# newwind.net
KiCad netlist of a schematic drawn in Altium Designer
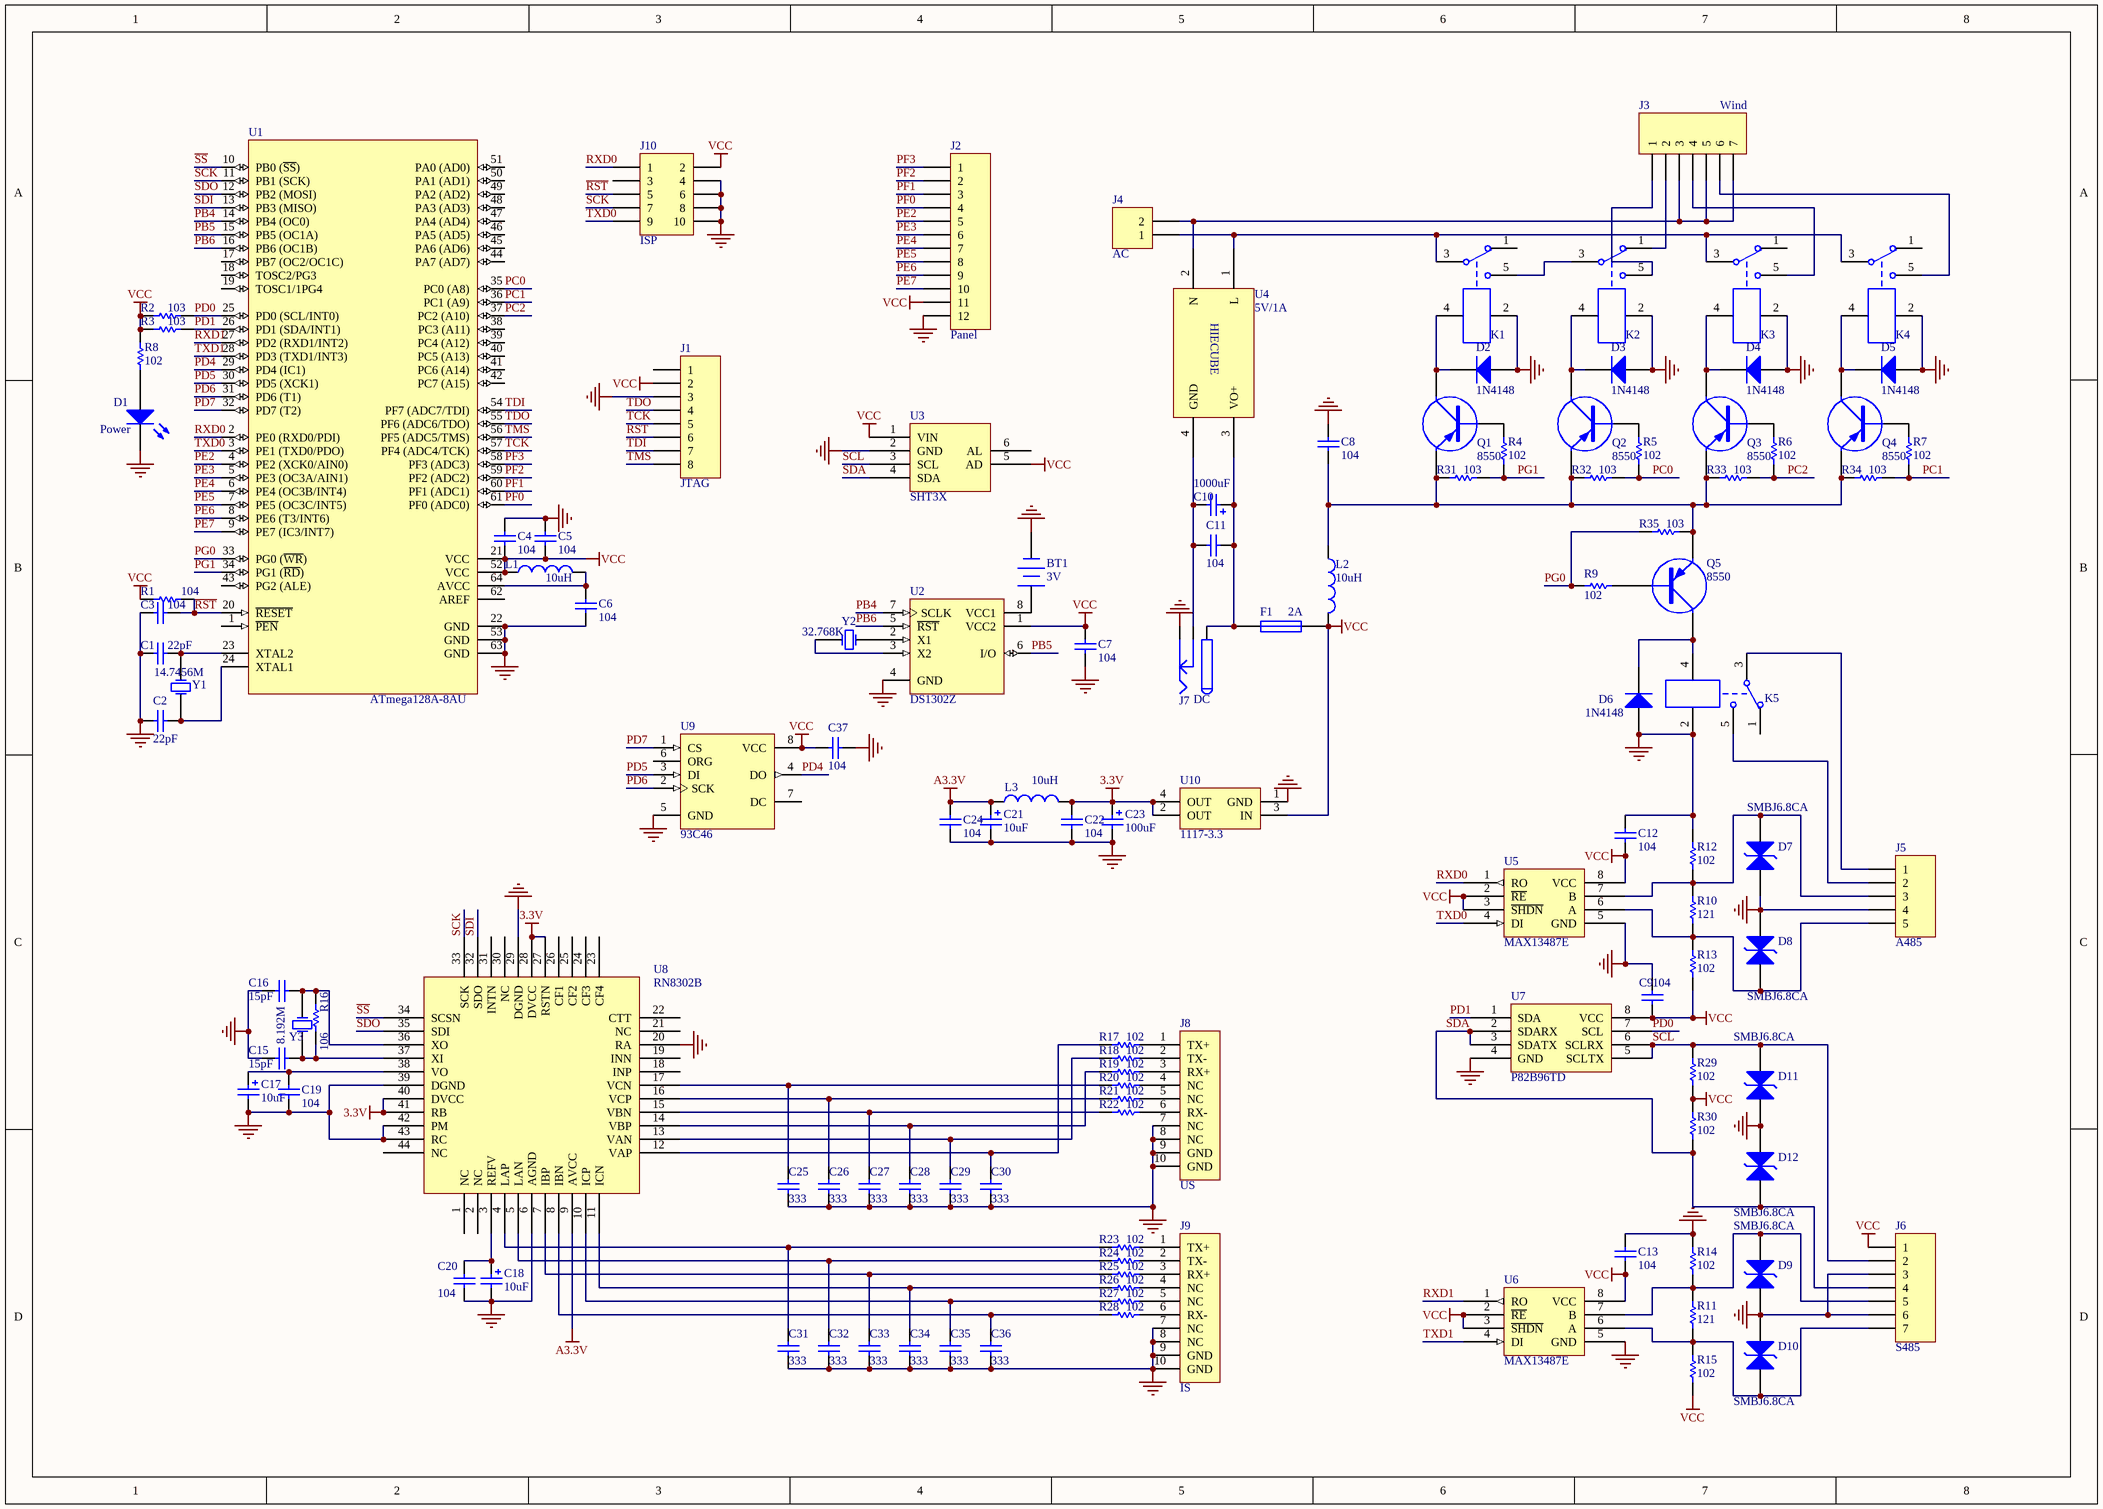
[diagram p0: newwind.SchDoc]

(export (version "E")
  (design (tool "Eeschema 10.0.6"))
  (components
    (comp (ref "BT1")
      (value "3V")
      (footprint "CR2032")
      (description "Multicell Battery")
      (fields (field (name "PUBLISHER") "*"))
      (libsource (lib "UC-EDAV4sch") (part "Battery"))
    )
    (comp (ref "C1")
      (value "22pF")
      (footprint "0805")
      (description "Capacitor")
      (fields (field (name "PUBLISHER") "*"))
      (libsource (lib "UC-MEGA128V1sch") (part "Cap1"))
    )
    (comp (ref "C2")
      (value "22pF")
      (footprint "0805")
      (description "Capacitor")
      (fields (field (name "PUBLISHER") "*"))
      (libsource (lib "UC-MEGA128V1sch") (part "Cap1"))
    )
    (comp (ref "C3")
      (value "104")
      (footprint "0805")
      (description "Capacitor")
      (fields (field (name "PUBLISHER") "*"))
      (libsource (lib "UC-MEGA128V1sch") (part "Cap1"))
    )
    (comp (ref "C4")
      (value "104")
      (footprint "0805")
      (description "Capacitor")
      (fields (field (name "PUBLISHER") "*"))
      (libsource (lib "UC-MEGA128V1sch") (part "Cap1"))
    )
    (comp (ref "C5")
      (value "104")
      (footprint "0805")
      (description "Capacitor")
      (fields (field (name "PUBLISHER") "*"))
      (libsource (lib "UC-MEGA128V1sch") (part "Cap1"))
    )
    (comp (ref "C6")
      (value "104")
      (footprint "0805")
      (description "Capacitor")
      (fields (field (name "PUBLISHER") "*"))
      (libsource (lib "UC-MEGA128V1sch") (part "Cap1"))
    )
    (comp (ref "C7")
      (value "104")
      (footprint "0805")
      (description "Capacitor")
      (fields (field (name "PUBLISHER") "*"))
      (libsource (lib "UC-MEGA128V1sch") (part "Cap1"))
    )
    (comp (ref "C8")
      (value "104")
      (footprint "0805")
      (description "Capacitor")
      (fields (field (name "PUBLISHER") "*"))
      (libsource (lib "UC-MEGA128V1sch") (part "Cap1"))
    )
    (comp (ref "C9")
      (value "104")
      (footprint "0805")
      (description "Capacitor")
      (fields (field (name "PUBLISHER") "*"))
      (libsource (lib "UC-MEGA128V1sch") (part "Cap1"))
    )
    (comp (ref "C10")
      (value "1000uF")
      (footprint "C10")
      (description "电解电容")
      (fields (field (name "PUBLISHER") "Altium Limited"))
      (libsource (lib "UC-SCH") (part "Cap2"))
    )
    (comp (ref "C11")
      (value "104")
      (footprint "0805")
      (description "Capacitor")
      (fields (field (name "PUBLISHER") "*"))
      (libsource (lib "UC-MEGA128V1sch") (part "Cap1"))
    )
    (comp (ref "C12")
      (value "104")
      (footprint "0805")
      (description "Capacitor")
      (fields (field (name "PUBLISHER") "*"))
      (libsource (lib "UC-MEGA128V1sch") (part "Cap1"))
    )
    (comp (ref "C13")
      (value "104")
      (footprint "0805")
      (description "Capacitor")
      (fields (field (name "PUBLISHER") "*"))
      (libsource (lib "UC-MEGA128V1sch") (part "Cap1"))
    )
    (comp (ref "C15")
      (value "15pF")
      (footprint "0805")
      (description "Capacitor")
      (fields (field (name "PUBLISHER") "*"))
      (libsource (lib "UC-MEGA128V1sch") (part "Cap1"))
    )
    (comp (ref "C16")
      (value "15pF")
      (footprint "0805")
      (description "Capacitor")
      (fields (field (name "PUBLISHER") "*"))
      (libsource (lib "UC-MEGA128V1sch") (part "Cap1"))
    )
    (comp (ref "C17")
      (value "10uF")
      (footprint "C1206")
      (description "电解电容")
      (fields (field (name "PUBLISHER") "Altium Limited"))
      (libsource (lib "UC-SCH") (part "Cap2"))
    )
    (comp (ref "C18")
      (value "10uF")
      (footprint "C1206")
      (description "电解电容")
      (fields (field (name "PUBLISHER") "Altium Limited"))
      (libsource (lib "UC-SCH") (part "Cap2"))
    )
    (comp (ref "C19")
      (value "104")
      (footprint "0805")
      (description "Capacitor")
      (fields (field (name "PUBLISHER") "*"))
      (libsource (lib "UC-MEGA128V1sch") (part "Cap1"))
    )
    (comp (ref "C20")
      (value "104")
      (footprint "0805")
      (description "Capacitor")
      (fields (field (name "PUBLISHER") "*"))
      (libsource (lib "UC-MEGA128V1sch") (part "Cap1"))
    )
    (comp (ref "C21")
      (value "10uF")
      (footprint "C1206")
      (description "电解电容")
      (fields (field (name "PUBLISHER") "Altium Limited"))
      (libsource (lib "UC-SCH") (part "Cap2"))
    )
    (comp (ref "C22")
      (value "104")
      (footprint "0805")
      (description "Capacitor")
      (fields (field (name "PUBLISHER") "*"))
      (libsource (lib "UC-MEGA128V1sch") (part "Cap1"))
    )
    (comp (ref "C23")
      (value "100uF")
      (footprint "C1210")
      (description "电解电容")
      (fields (field (name "PUBLISHER") "Altium Limited"))
      (libsource (lib "UC-SCH") (part "Cap2"))
    )
    (comp (ref "C24")
      (value "104")
      (footprint "0805")
      (description "Capacitor")
      (fields (field (name "PUBLISHER") "*"))
      (libsource (lib "UC-MEGA128V1sch") (part "Cap1"))
    )
    (comp (ref "C25")
      (value "333")
      (footprint "0805")
      (description "Capacitor")
      (fields (field (name "PUBLISHER") "*"))
      (libsource (lib "UC-MEGA128V1sch") (part "Cap1"))
    )
    (comp (ref "C26")
      (value "333")
      (footprint "0805")
      (description "Capacitor")
      (fields (field (name "PUBLISHER") "*"))
      (libsource (lib "UC-MEGA128V1sch") (part "Cap1"))
    )
    (comp (ref "C27")
      (value "333")
      (footprint "0805")
      (description "Capacitor")
      (fields (field (name "PUBLISHER") "*"))
      (libsource (lib "UC-MEGA128V1sch") (part "Cap1"))
    )
    (comp (ref "C28")
      (value "333")
      (footprint "0805")
      (description "Capacitor")
      (fields (field (name "PUBLISHER") "*"))
      (libsource (lib "UC-MEGA128V1sch") (part "Cap1"))
    )
    (comp (ref "C29")
      (value "333")
      (footprint "0805")
      (description "Capacitor")
      (fields (field (name "PUBLISHER") "*"))
      (libsource (lib "UC-MEGA128V1sch") (part "Cap1"))
    )
    (comp (ref "C30")
      (value "333")
      (footprint "0805")
      (description "Capacitor")
      (fields (field (name "PUBLISHER") "*"))
      (libsource (lib "UC-MEGA128V1sch") (part "Cap1"))
    )
    (comp (ref "C31")
      (value "333")
      (footprint "0805")
      (description "Capacitor")
      (fields (field (name "PUBLISHER") "*"))
      (libsource (lib "UC-MEGA128V1sch") (part "Cap1"))
    )
    (comp (ref "C32")
      (value "333")
      (footprint "0805")
      (description "Capacitor")
      (fields (field (name "PUBLISHER") "*"))
      (libsource (lib "UC-MEGA128V1sch") (part "Cap1"))
    )
    (comp (ref "C33")
      (value "333")
      (footprint "0805")
      (description "Capacitor")
      (fields (field (name "PUBLISHER") "*"))
      (libsource (lib "UC-MEGA128V1sch") (part "Cap1"))
    )
    (comp (ref "C34")
      (value "333")
      (footprint "0805")
      (description "Capacitor")
      (fields (field (name "PUBLISHER") "*"))
      (libsource (lib "UC-MEGA128V1sch") (part "Cap1"))
    )
    (comp (ref "C35")
      (value "333")
      (footprint "0805")
      (description "Capacitor")
      (fields (field (name "PUBLISHER") "*"))
      (libsource (lib "UC-MEGA128V1sch") (part "Cap1"))
    )
    (comp (ref "C36")
      (value "333")
      (footprint "0805")
      (description "Capacitor")
      (fields (field (name "PUBLISHER") "*"))
      (libsource (lib "UC-MEGA128V1sch") (part "Cap1"))
    )
    (comp (ref "C37")
      (value "104")
      (footprint "0805")
      (description "Capacitor")
      (fields (field (name "PUBLISHER") "*"))
      (libsource (lib "UC-MEGA128V1sch") (part "Cap1"))
    )
    (comp (ref "D1")
      (value "Power")
      (footprint "LED-2P")
      (description "Typical INFRARED GaAs LED")
      (fields (field (name "PUBLISHER") "*"))
      (libsource (lib "UC-MEGA128V1sch") (part "LED"))
    )
    (comp (ref "D2")
      (value "1N4148")
      (footprint "1206")
      (description "Default Diode")
      (fields (field (name "PUBLISHER") "Altium Limited"))
      (libsource (lib "Miscellaneous Devices") (part "Diode"))
    )
    (comp (ref "D3")
      (value "1N4148")
      (footprint "1206")
      (description "Default Diode")
      (fields (field (name "PUBLISHER") "Altium Limited"))
      (libsource (lib "Miscellaneous Devices") (part "Diode"))
    )
    (comp (ref "D4")
      (value "1N4148")
      (footprint "1206")
      (description "Default Diode")
      (fields (field (name "PUBLISHER") "Altium Limited"))
      (libsource (lib "Miscellaneous Devices") (part "Diode"))
    )
    (comp (ref "D5")
      (value "1N4148")
      (footprint "1206")
      (description "Default Diode")
      (fields (field (name "PUBLISHER") "Altium Limited"))
      (libsource (lib "Miscellaneous Devices") (part "Diode"))
    )
    (comp (ref "D6")
      (value "1N4148")
      (footprint "1206")
      (description "Default Diode")
      (fields (field (name "PUBLISHER") "Altium Limited"))
      (libsource (lib "Miscellaneous Devices") (part "Diode"))
    )
    (comp (ref "D7")
      (value "SMBJ6.8CA")
      (footprint "SMB")
      (fields (field (name "PUBLISHER") "Altium Limited"))
      (libsource (lib "UC-SCH") (part "TVS"))
    )
    (comp (ref "D8")
      (value "SMBJ6.8CA")
      (footprint "SMB")
      (fields (field (name "PUBLISHER") "Altium Limited"))
      (libsource (lib "UC-SCH") (part "TVS"))
    )
    (comp (ref "D9")
      (value "SMBJ6.8CA")
      (footprint "SMB")
      (fields (field (name "PUBLISHER") "Altium Limited"))
      (libsource (lib "UC-SCH") (part "TVS"))
    )
    (comp (ref "D10")
      (value "SMBJ6.8CA")
      (footprint "SMB")
      (fields (field (name "PUBLISHER") "Altium Limited"))
      (libsource (lib "UC-SCH") (part "TVS"))
    )
    (comp (ref "D11")
      (value "SMBJ6.8CA")
      (footprint "SMB")
      (fields (field (name "PUBLISHER") "Altium Limited"))
      (libsource (lib "UC-SCH") (part "TVS"))
    )
    (comp (ref "D12")
      (value "SMBJ6.8CA")
      (footprint "SMB")
      (fields (field (name "PUBLISHER") "Altium Limited"))
      (libsource (lib "UC-SCH") (part "TVS"))
    )
    (comp (ref "F1")
      (value "2A")
      (footprint "1812")
      (description "Fuse")
      (fields (field (name "PUBLISHER") "Altium Limited"))
      (libsource (lib "Miscellaneous Devices") (part "Fuse 1"))
    )
    (comp (ref "J1")
      (value "JTAG")
      (footprint "CON8")
      (description "Header, 8-Pin")
      (fields (field (name "PUBLISHER") "Altium Limited"))
      (libsource (lib "Miscellaneous Connectors") (part "MHDR1X8"))
    )
    (comp (ref "J2")
      (value "Panel")
      (footprint "XH2.54-12P")
      (description "Header, 12-Pin")
      (fields (field (name "PUBLISHER") "Altium Limited"))
      (libsource (lib "Miscellaneous Connectors") (part "Header 12"))
    )
    (comp (ref "J3")
      (value "Wind")
      (footprint "2EDG-3.81-7P")
      (description "Header, 7-Pin")
      (fields (field (name "PUBLISHER") "Altium Limited"))
      (libsource (lib "") (part "MHDR1X7_1"))
    )
    (comp (ref "J4")
      (value "AC")
      (footprint "2EDG-3.81-2P")
      (description "Header, 2-Pin")
      (fields (field (name "PUBLISHER") "Altium Limited"))
      (libsource (lib "Miscellaneous Connectors") (part "MHDR1X2"))
    )
    (comp (ref "J5")
      (value "A485")
      (footprint "2EDG-3.81-5P")
      (description "Header, 5-Pin")
      (fields (field (name "PUBLISHER") "Altium Limited"))
      (libsource (lib "Miscellaneous Connectors") (part "MHDR1X5"))
    )
    (comp (ref "J6")
      (value "S485")
      (footprint "2EDG-3.81-7P")
      (description "Header, 7-Pin")
      (fields (field (name "PUBLISHER") "Altium Limited"))
      (libsource (lib "Miscellaneous Connectors") (part "MHDR1X7"))
    )
    (comp (ref "J7")
      (value "DC")
      (footprint "PWR2.5")
      (description "2.5电源插座")
      (fields (field (name "PUBLISHER") "Altium Limited"))
      (libsource (lib "UC-SCH") (part "PWR2.5"))
    )
    (comp (ref "J8")
      (value "US")
      (footprint "RJ-45")
      (description "RJ45水晶座")
      (libsource (lib "UC-SCH") (part "RJ45"))
    )
    (comp (ref "J9")
      (value "IS")
      (footprint "RJ-45")
      (description "RJ45水晶座")
      (libsource (lib "UC-SCH") (part "RJ45"))
    )
    (comp (ref "J10")
      (value "ISP")
      (footprint "DC3-10")
      (description "Header, 5-Pin, Dual row")
      (fields (field (name "PUBLISHER") "*"))
      (libsource (lib "UC-MEGA128V1sch") (part "Header 5X2"))
    )
    (comp (ref "K1")
      (value "~")
      (footprint "T73")
      (description "6脚继电器")
      (libsource (lib "UC-EDAV4sch") (part "Relay-6P"))
    )
    (comp (ref "K2")
      (value "~")
      (footprint "T73")
      (description "6脚继电器")
      (libsource (lib "UC-EDAV4sch") (part "Relay-6P"))
    )
    (comp (ref "K3")
      (value "~")
      (footprint "T73")
      (description "6脚继电器")
      (libsource (lib "UC-EDAV4sch") (part "Relay-6P"))
    )
    (comp (ref "K4")
      (value "~")
      (footprint "T73")
      (description "6脚继电器")
      (libsource (lib "UC-EDAV4sch") (part "Relay-6P"))
    )
    (comp (ref "K5")
      (value "~")
      (footprint "T73")
      (description "6脚继电器")
      (libsource (lib "UC-EDAV4sch") (part "Relay-6P"))
    )
    (comp (ref "L1")
      (value "10uH")
      (footprint "0805")
      (description "Inductor")
      (fields (field (name "PUBLISHER") "*"))
      (libsource (lib "UC-MEGA128V1sch") (part "Inductor"))
    )
    (comp (ref "L2")
      (value "10uH")
      (footprint "0805")
      (description "Inductor")
      (fields (field (name "PUBLISHER") "Altium Limited"))
      (libsource (lib "WeijaySch") (part "Inductor"))
    )
    (comp (ref "L3")
      (value "10uH")
      (footprint "0805")
      (description "Inductor")
      (fields (field (name "PUBLISHER") "Altium Limited"))
      (libsource (lib "WeijaySch") (part "Inductor"))
    )
    (comp (ref "Q1")
      (value "8550")
      (footprint "SOT-23-3")
      (description "PNP三极管")
      (libsource (lib "WeijaySch") (part "8550"))
    )
    (comp (ref "Q2")
      (value "8550")
      (footprint "SOT-23-3")
      (description "PNP三极管")
      (libsource (lib "WeijaySch") (part "8550"))
    )
    (comp (ref "Q3")
      (value "8550")
      (footprint "SOT-23-3")
      (description "PNP三极管")
      (libsource (lib "WeijaySch") (part "8550"))
    )
    (comp (ref "Q4")
      (value "8550")
      (footprint "SOT-23-3")
      (description "PNP三极管")
      (libsource (lib "WeijaySch") (part "8550"))
    )
    (comp (ref "Q5")
      (value "8550")
      (footprint "SOT-23-3")
      (description "PNP三极管")
      (libsource (lib "WeijaySch") (part "8550"))
    )
    (comp (ref "R1")
      (value "104")
      (footprint "0805")
      (description "Resistor")
      (fields (field (name "PUBLISHER") "*"))
      (libsource (lib "UC-MEGA128V1sch") (part "Res"))
    )
    (comp (ref "R2")
      (value "103")
      (footprint "0805")
      (description "Resistor")
      (fields (field (name "PUBLISHER") "*"))
      (libsource (lib "UC-MEGA128V1sch") (part "Res"))
    )
    (comp (ref "R3")
      (value "103")
      (footprint "0805")
      (description "Resistor")
      (fields (field (name "PUBLISHER") "*"))
      (libsource (lib "UC-MEGA128V1sch") (part "Res"))
    )
    (comp (ref "R4")
      (value "102")
      (footprint "0805")
      (description "Resistor")
      (fields (field (name "PUBLISHER") "Altium Limited"))
      (libsource (lib "WeijaySch") (part "Res"))
    )
    (comp (ref "R5")
      (value "102")
      (footprint "0805")
      (description "Resistor")
      (fields (field (name "PUBLISHER") "Altium Limited"))
      (libsource (lib "WeijaySch") (part "Res"))
    )
    (comp (ref "R6")
      (value "102")
      (footprint "0805")
      (description "Resistor")
      (fields (field (name "PUBLISHER") "Altium Limited"))
      (libsource (lib "WeijaySch") (part "Res"))
    )
    (comp (ref "R7")
      (value "102")
      (footprint "0805")
      (description "Resistor")
      (fields (field (name "PUBLISHER") "Altium Limited"))
      (libsource (lib "WeijaySch") (part "Res"))
    )
    (comp (ref "R8")
      (value "102")
      (footprint "0805")
      (description "Resistor")
      (fields (field (name "PUBLISHER") "Altium Limited"))
      (libsource (lib "WeijaySch") (part "Res"))
    )
    (comp (ref "R9")
      (value "102")
      (footprint "0805")
      (description "Resistor")
      (fields (field (name "PUBLISHER") "Altium Limited"))
      (libsource (lib "WeijaySch") (part "Res"))
    )
    (comp (ref "R10")
      (value "121")
      (footprint "0805")
      (description "Resistor")
      (fields (field (name "PUBLISHER") "Altium Limited"))
      (libsource (lib "WeijaySch") (part "Res"))
    )
    (comp (ref "R11")
      (value "121")
      (footprint "0805")
      (description "Resistor")
      (fields (field (name "PUBLISHER") "Altium Limited"))
      (libsource (lib "WeijaySch") (part "Res"))
    )
    (comp (ref "R12")
      (value "102")
      (footprint "0805")
      (description "Resistor")
      (fields (field (name "PUBLISHER") "Altium Limited"))
      (libsource (lib "WeijaySch") (part "Res"))
    )
    (comp (ref "R13")
      (value "102")
      (footprint "0805")
      (description "Resistor")
      (fields (field (name "PUBLISHER") "Altium Limited"))
      (libsource (lib "WeijaySch") (part "Res"))
    )
    (comp (ref "R14")
      (value "102")
      (footprint "0805")
      (description "Resistor")
      (fields (field (name "PUBLISHER") "Altium Limited"))
      (libsource (lib "WeijaySch") (part "Res"))
    )
    (comp (ref "R15")
      (value "102")
      (footprint "0805")
      (description "Resistor")
      (fields (field (name "PUBLISHER") "Altium Limited"))
      (libsource (lib "WeijaySch") (part "Res"))
    )
    (comp (ref "R16")
      (value "106")
      (footprint "0805")
      (description "Resistor")
      (fields (field (name "PUBLISHER") "Altium Limited"))
      (libsource (lib "WeijaySch") (part "Res"))
    )
    (comp (ref "R17")
      (value "102")
      (footprint "0805")
      (description "Resistor")
      (fields (field (name "PUBLISHER") "Altium Limited"))
      (libsource (lib "WeijaySch") (part "Res"))
    )
    (comp (ref "R18")
      (value "102")
      (footprint "0805")
      (description "Resistor")
      (fields (field (name "PUBLISHER") "Altium Limited"))
      (libsource (lib "WeijaySch") (part "Res"))
    )
    (comp (ref "R19")
      (value "102")
      (footprint "0805")
      (description "Resistor")
      (fields (field (name "PUBLISHER") "Altium Limited"))
      (libsource (lib "WeijaySch") (part "Res"))
    )
    (comp (ref "R20")
      (value "102")
      (footprint "0805")
      (description "Resistor")
      (fields (field (name "PUBLISHER") "Altium Limited"))
      (libsource (lib "WeijaySch") (part "Res"))
    )
    (comp (ref "R21")
      (value "102")
      (footprint "0805")
      (description "Resistor")
      (fields (field (name "PUBLISHER") "Altium Limited"))
      (libsource (lib "WeijaySch") (part "Res"))
    )
    (comp (ref "R22")
      (value "102")
      (footprint "0805")
      (description "Resistor")
      (fields (field (name "PUBLISHER") "Altium Limited"))
      (libsource (lib "WeijaySch") (part "Res"))
    )
    (comp (ref "R23")
      (value "102")
      (footprint "0805")
      (description "Resistor")
      (fields (field (name "PUBLISHER") "Altium Limited"))
      (libsource (lib "WeijaySch") (part "Res"))
    )
    (comp (ref "R24")
      (value "102")
      (footprint "0805")
      (description "Resistor")
      (fields (field (name "PUBLISHER") "Altium Limited"))
      (libsource (lib "WeijaySch") (part "Res"))
    )
    (comp (ref "R25")
      (value "102")
      (footprint "0805")
      (description "Resistor")
      (fields (field (name "PUBLISHER") "Altium Limited"))
      (libsource (lib "WeijaySch") (part "Res"))
    )
    (comp (ref "R26")
      (value "102")
      (footprint "0805")
      (description "Resistor")
      (fields (field (name "PUBLISHER") "Altium Limited"))
      (libsource (lib "WeijaySch") (part "Res"))
    )
    (comp (ref "R27")
      (value "102")
      (footprint "0805")
      (description "Resistor")
      (fields (field (name "PUBLISHER") "Altium Limited"))
      (libsource (lib "WeijaySch") (part "Res"))
    )
    (comp (ref "R28")
      (value "102")
      (footprint "0805")
      (description "Resistor")
      (fields (field (name "PUBLISHER") "Altium Limited"))
      (libsource (lib "WeijaySch") (part "Res"))
    )
    (comp (ref "R29")
      (value "102")
      (footprint "0805")
      (description "Resistor")
      (fields (field (name "PUBLISHER") "Altium Limited"))
      (libsource (lib "WeijaySch") (part "Res"))
    )
    (comp (ref "R30")
      (value "102")
      (footprint "0805")
      (description "Resistor")
      (fields (field (name "PUBLISHER") "Altium Limited"))
      (libsource (lib "WeijaySch") (part "Res"))
    )
    (comp (ref "R31")
      (value "103")
      (footprint "0805")
      (description "Resistor")
      (fields (field (name "PUBLISHER") "*"))
      (libsource (lib "UC-MEGA128V1sch") (part "Res"))
    )
    (comp (ref "R32")
      (value "103")
      (footprint "0805")
      (description "Resistor")
      (fields (field (name "PUBLISHER") "*"))
      (libsource (lib "UC-MEGA128V1sch") (part "Res"))
    )
    (comp (ref "R33")
      (value "103")
      (footprint "0805")
      (description "Resistor")
      (fields (field (name "PUBLISHER") "*"))
      (libsource (lib "UC-MEGA128V1sch") (part "Res"))
    )
    (comp (ref "R34")
      (value "103")
      (footprint "0805")
      (description "Resistor")
      (fields (field (name "PUBLISHER") "*"))
      (libsource (lib "UC-MEGA128V1sch") (part "Res"))
    )
    (comp (ref "R35")
      (value "103")
      (footprint "0805")
      (description "Resistor")
      (fields (field (name "PUBLISHER") "*"))
      (libsource (lib "UC-MEGA128V1sch") (part "Res"))
    )
    (comp (ref "U1")
      (value "ATmega128A-8AU")
      (footprint "ATMega128")
      (description "8-Bit AVR Microcontroller with 128K Bytes of In-System Programmable Flash Memory")
      (fields (field (name "PUBLISHER") "*"))
      (libsource (lib "UC-MEGA128V1sch") (part "ATmega128L-8AC"))
    )
    (comp (ref "U2")
      (value "DS1302Z")
      (footprint "SOP-8P-3.9")
      (description "Trickle Charge Timekeeping Chip")
      (fields (field (name "PUBLISHER") "Altium Limited"))
      (libsource (lib "Dallas Peripheral Real Time Clock") (part "DS1302Z"))
    )
    (comp (ref "U3") (value "SHT3X") (footprint "SHT3X") (libsource (lib "UC-SCH") (part "SHT3X")))
    (comp (ref "U4")
      (value "5V/1A")
      (footprint "HIECUBE12W")
      (description "12W单输出模块")
      (libsource (lib "UC-SCH") (part "HIECUBE12W"))
    )
    (comp (ref "U5")
      (value "MAX13487E")
      (footprint "SOP-8P-3.9")
      (libsource (lib "UC-SCH") (part "MAX13487E"))
    )
    (comp (ref "U6")
      (value "MAX13487E")
      (footprint "SOP-8P-3.9")
      (libsource (lib "UC-SCH") (part "MAX13487E"))
    )
    (comp (ref "U7") (value "P82B96TD") (footprint "SOP-8P-3.9") (libsource (lib "UC-SCH") (part "P82B96TD")))
    (comp (ref "U8") (value "RN8302B") (footprint "QFP-44P-0.8") (libsource (lib "UC-SCH") (part "RN8302B")))
    (comp (ref "U9")
      (value "93C46")
      (footprint "SOP-8P-3.9")
      (description "SPI EEPROM")
      (fields (field (name "PUBLISHER") "Altium Limited"))
      (libsource (lib "UC-SCH") (part "93C46"))
    )
    (comp (ref "U10")
      (value "1117-3.3")
      (footprint "SOT-223")
      (description "800mA 稳压")
      (fields (field (name "PUBLISHER") "Altium Limited"))
      (libsource (lib "UC-SCH") (part "1117"))
    )
    (comp (ref "Y1")
      (value "14.7456M")
      (footprint "CRYSTAL-2P")
      (description "Crystal Oscillator")
      (fields (field (name "PUBLISHER") "*"))
      (libsource (lib "UC-MEGA128V1sch") (part "CRYSTAL-2"))
    )
    (comp (ref "Y2")
      (value "32.768K")
      (footprint "32.768K")
      (description "Crystal Oscillator")
      (fields (field (name "PUBLISHER") "*"))
      (libsource (lib "UC-MEGA128V1sch") (part "CRYSTAL-2"))
    )
    (comp (ref "Y3")
      (value "8.192M")
      (footprint "CRYSTAL-2P")
      (description "Crystal Oscillator")
      (fields (field (name "PUBLISHER") "*"))
      (libsource (lib "UC-MEGA128V1sch") (part "CRYSTAL-2"))
    )
  )
  (nets
    (net (code "1") (name "/PB4") (class "Default")
      (node (ref "U1") (pin "14") (pinfunction "PB4_(OC0)_14") (pintype "bidirectional"))
      (node (ref "U2") (pin "7") (pinfunction "SCLK_7") (pintype "input"))
    )
    (net (code "2") (name "/PB5") (class "Default")
      (node (ref "U1") (pin "15") (pinfunction "PB5_(OC1A)_15") (pintype "bidirectional"))
      (node (ref "U2") (pin "6") (pinfunction "I/O_6") (pintype "bidirectional"))
    )
    (net (code "3") (name "/PB6") (class "Default")
      (node (ref "U1") (pin "16") (pinfunction "PB6_(OC1B)_16") (pintype "bidirectional"))
      (node (ref "U2") (pin "5") (pinfunction "~{RST}_5") (pintype "input"))
    )
    (net (code "4") (name "/PC0") (class "Default")
      (node (ref "R32") (pin "2") (pinfunction "2_2") (pintype "passive"))
      (node (ref "R5") (pin "1") (pinfunction "1_1") (pintype "passive"))
      (node (ref "U1") (pin "35") (pinfunction "PC0_(A8)_35") (pintype "bidirectional"))
    )
    (net (code "5") (name "/PC1") (class "Default")
      (node (ref "R34") (pin "2") (pinfunction "2_2") (pintype "passive"))
      (node (ref "R7") (pin "1") (pinfunction "1_1") (pintype "passive"))
      (node (ref "U1") (pin "36") (pinfunction "PC1_(A9)_36") (pintype "bidirectional"))
    )
    (net (code "6") (name "/PC2") (class "Default")
      (node (ref "R33") (pin "2") (pinfunction "2_2") (pintype "passive"))
      (node (ref "R6") (pin "1") (pinfunction "1_1") (pintype "passive"))
      (node (ref "U1") (pin "37") (pinfunction "PC2_(A10)_37") (pintype "bidirectional"))
    )
    (net (code "7") (name "/PD0") (class "Default")
      (node (ref "R2") (pin "2") (pinfunction "2_2") (pintype "passive"))
      (node (ref "U1") (pin "25") (pinfunction "PD0_(SCL/INT0)_25") (pintype "bidirectional"))
      (node (ref "U7") (pin "7") (pinfunction "SCL_7") (pintype "passive"))
    )
    (net (code "8") (name "/PD1") (class "Default")
      (node (ref "R3") (pin "2") (pinfunction "2_2") (pintype "passive"))
      (node (ref "U1") (pin "26") (pinfunction "PD1_(SDA/INT1)_26") (pintype "bidirectional"))
      (node (ref "U7") (pin "1") (pinfunction "SDA_1") (pintype "passive"))
    )
    (net (code "9") (name "/PD4") (class "Default")
      (node (ref "U1") (pin "29") (pinfunction "PD4_(IC1)_29") (pintype "bidirectional"))
      (node (ref "U9") (pin "4") (pinfunction "DO_4") (pintype "output"))
    )
    (net (code "10") (name "/PD5") (class "Default")
      (node (ref "U1") (pin "30") (pinfunction "PD5_(XCK1)_30") (pintype "bidirectional"))
      (node (ref "U9") (pin "3") (pinfunction "DI_3") (pintype "input"))
    )
    (net (code "11") (name "/PD6") (class "Default")
      (node (ref "U1") (pin "31") (pinfunction "PD6_(T1)_31") (pintype "bidirectional"))
      (node (ref "U9") (pin "2") (pinfunction "SCK_2") (pintype "input"))
    )
    (net (code "12") (name "/PD7") (class "Default")
      (node (ref "U1") (pin "32") (pinfunction "PD7_(T2)_32") (pintype "bidirectional"))
      (node (ref "U9") (pin "1") (pinfunction "CS_1") (pintype "input"))
    )
    (net (code "13") (name "/PE2") (class "Default")
      (node (ref "J2") (pin "5") (pinfunction "5_5") (pintype "passive"))
      (node (ref "U1") (pin "4") (pinfunction "PE2_(XCK0/AIN0)_4") (pintype "bidirectional"))
    )
    (net (code "14") (name "/PE3") (class "Default")
      (node (ref "J2") (pin "6") (pinfunction "6_6") (pintype "passive"))
      (node (ref "U1") (pin "5") (pinfunction "PE3_(OC3A/AIN1)_5") (pintype "bidirectional"))
    )
    (net (code "15") (name "/PE4") (class "Default")
      (node (ref "J2") (pin "7") (pinfunction "7_7") (pintype "passive"))
      (node (ref "U1") (pin "6") (pinfunction "PE4_(OC3B/INT4)_6") (pintype "bidirectional"))
    )
    (net (code "16") (name "/PE5") (class "Default")
      (node (ref "J2") (pin "8") (pinfunction "8_8") (pintype "passive"))
      (node (ref "U1") (pin "7") (pinfunction "PE5_(OC3C/INT5)_7") (pintype "bidirectional"))
    )
    (net (code "17") (name "/PE6") (class "Default")
      (node (ref "J2") (pin "9") (pinfunction "9_9") (pintype "passive"))
      (node (ref "U1") (pin "8") (pinfunction "PE6_(T3/INT6)_8") (pintype "bidirectional"))
    )
    (net (code "18") (name "/PE7") (class "Default")
      (node (ref "J2") (pin "10") (pinfunction "10_10") (pintype "passive"))
      (node (ref "U1") (pin "9") (pinfunction "PE7_(IC3/INT7)_9") (pintype "bidirectional"))
    )
    (net (code "19") (name "/PF0") (class "Default")
      (node (ref "J2") (pin "4") (pinfunction "4_4") (pintype "passive"))
      (node (ref "U1") (pin "61") (pinfunction "PF0_(ADC0)_61") (pintype "bidirectional"))
    )
    (net (code "20") (name "/PF1") (class "Default")
      (node (ref "J2") (pin "3") (pinfunction "3_3") (pintype "passive"))
      (node (ref "U1") (pin "60") (pinfunction "PF1_(ADC1)_60") (pintype "bidirectional"))
    )
    (net (code "21") (name "/PF2") (class "Default")
      (node (ref "J2") (pin "2") (pinfunction "2_2") (pintype "passive"))
      (node (ref "U1") (pin "59") (pinfunction "PF2_(ADC2)_59") (pintype "bidirectional"))
    )
    (net (code "22") (name "/PF3") (class "Default")
      (node (ref "J2") (pin "1") (pinfunction "1_1") (pintype "passive"))
      (node (ref "U1") (pin "58") (pinfunction "PF3_(ADC3)_58") (pintype "bidirectional"))
    )
    (net (code "23") (name "/PG0") (class "Default")
      (node (ref "R35") (pin "1") (pinfunction "1_1") (pintype "passive"))
      (node (ref "R9") (pin "2") (pinfunction "2_2") (pintype "passive"))
      (node (ref "U1") (pin "33") (pinfunction "PG0_(~{WR})_33") (pintype "bidirectional"))
    )
    (net (code "24") (name "/PG1") (class "Default")
      (node (ref "R31") (pin "2") (pinfunction "2_2") (pintype "passive"))
      (node (ref "R4") (pin "1") (pinfunction "1_1") (pintype "passive"))
      (node (ref "U1") (pin "34") (pinfunction "PG1_(~{RD})_34") (pintype "bidirectional"))
    )
    (net (code "25") (name "/RXD0") (class "Default")
      (node (ref "J10") (pin "1") (pinfunction "1_1") (pintype "passive"))
      (node (ref "U1") (pin "2") (pinfunction "PE0_(RXD0/PDI)_2") (pintype "bidirectional"))
      (node (ref "U5") (pin "1") (pinfunction "RO_1") (pintype "output"))
    )
    (net (code "26") (name "/RXD1") (class "Default")
      (node (ref "U1") (pin "27") (pinfunction "PD2_(RXD1/INT2)_27") (pintype "bidirectional"))
      (node (ref "U6") (pin "1") (pinfunction "RO_1") (pintype "output"))
    )
    (net (code "27") (name "/SCK") (class "Default")
      (node (ref "J10") (pin "7") (pinfunction "7_7") (pintype "passive"))
      (node (ref "U1") (pin "11") (pinfunction "PB1_(SCK)_11") (pintype "bidirectional"))
      (node (ref "U8") (pin "33") (pinfunction "SCK_33") (pintype "passive"))
    )
    (net (code "28") (name "/SCL") (class "Default")
      (node (ref "D11") (pin "1") (pinfunction "A_1") (pintype "passive"))
      (node (ref "J6") (pin "2") (pinfunction "2_2") (pintype "passive"))
      (node (ref "R29") (pin "2") (pinfunction "2_2") (pintype "passive"))
      (node (ref "U3") (pin "3") (pinfunction "SCL_3") (pintype "passive"))
      (node (ref "U7") (pin "5") (pinfunction "SCLTX_5") (pintype "passive"))
      (node (ref "U7") (pin "6") (pinfunction "SCLRX_6") (pintype "passive"))
    )
    (net (code "29") (name "/SDA") (class "Default")
      (node (ref "D12") (pin "2") (pinfunction "K_2") (pintype "passive"))
      (node (ref "J6") (pin "4") (pinfunction "4_4") (pintype "passive"))
      (node (ref "R30") (pin "1") (pinfunction "1_1") (pintype "passive"))
      (node (ref "U3") (pin "4") (pinfunction "SDA_4") (pintype "passive"))
      (node (ref "U7") (pin "2") (pinfunction "SDARX_2") (pintype "passive"))
      (node (ref "U7") (pin "3") (pinfunction "SDATX_3") (pintype "passive"))
    )
    (net (code "30") (name "/SDI") (class "Default")
      (node (ref "U1") (pin "13") (pinfunction "PB3_(MISO)_13") (pintype "bidirectional"))
      (node (ref "U8") (pin "32") (pinfunction "SDO_32") (pintype "passive"))
    )
    (net (code "31") (name "/SDO") (class "Default")
      (node (ref "U1") (pin "12") (pinfunction "PB2_(MOSI)_12") (pintype "bidirectional"))
      (node (ref "U8") (pin "35") (pinfunction "SDI_35") (pintype "passive"))
    )
    (net (code "32") (name "/TCK") (class "Default")
      (node (ref "J1") (pin "5") (pinfunction "5_5") (pintype "passive"))
      (node (ref "U1") (pin "57") (pinfunction "PF4_(ADC4/TCK)_57") (pintype "bidirectional"))
    )
    (net (code "33") (name "/TDI") (class "Default")
      (node (ref "J1") (pin "7") (pinfunction "7_7") (pintype "passive"))
      (node (ref "U1") (pin "54") (pinfunction "PF7_(ADC7/TDI)_54") (pintype "bidirectional"))
    )
    (net (code "34") (name "/TDO") (class "Default")
      (node (ref "J1") (pin "4") (pinfunction "4_4") (pintype "passive"))
      (node (ref "U1") (pin "55") (pinfunction "PF6_(ADC6/TDO)_55") (pintype "bidirectional"))
    )
    (net (code "35") (name "/TMS") (class "Default")
      (node (ref "J1") (pin "8") (pinfunction "8_8") (pintype "passive"))
      (node (ref "U1") (pin "56") (pinfunction "PF5_(ADC5/TMS)_56") (pintype "bidirectional"))
    )
    (net (code "36") (name "/TXD0") (class "Default")
      (node (ref "J10") (pin "9") (pinfunction "9_9") (pintype "passive"))
      (node (ref "U1") (pin "3") (pinfunction "PE1_(TXD0/PDO)_3") (pintype "bidirectional"))
      (node (ref "U5") (pin "4") (pinfunction "DI_4") (pintype "input"))
    )
    (net (code "37") (name "/TXD1") (class "Default")
      (node (ref "U1") (pin "28") (pinfunction "PD3_(TXD1/INT3)_28") (pintype "bidirectional"))
      (node (ref "U6") (pin "4") (pinfunction "DI_4") (pintype "input"))
    )
    (net (code "38") (name "/~{RST}") (class "Default")
      (node (ref "C3") (pin "2") (pinfunction "2_2") (pintype "passive"))
      (node (ref "J1") (pin "6") (pinfunction "6_6") (pintype "passive"))
      (node (ref "J10") (pin "5") (pinfunction "5_5") (pintype "passive"))
      (node (ref "R1") (pin "2") (pinfunction "2_2") (pintype "passive"))
      (node (ref "U1") (pin "20") (pinfunction "~{RESET}_20") (pintype "input"))
    )
    (net (code "39") (name "/~{SS}") (class "Default")
      (node (ref "U1") (pin "10") (pinfunction "PB0_(~{SS})_10") (pintype "bidirectional"))
      (node (ref "U8") (pin "34") (pinfunction "SCSN_34") (pintype "passive"))
    )
    (net (code "40") (name "3.3V") (class "Default")
      (node (ref "C22") (pin "2") (pinfunction "2_2") (pintype "passive"))
      (node (ref "C23") (pin "1") (pinfunction "1_1") (pintype "passive"))
      (node (ref "L3") (pin "2") (pinfunction "2_2") (pintype "passive"))
      (node (ref "U10") (pin "2") (pinfunction "OUT_2") (pintype "power_in"))
      (node (ref "U10") (pin "4") (pinfunction "OUT_4") (pintype "power_in"))
      (node (ref "U8") (pin "27") (pinfunction "RSTN_27") (pintype "passive"))
      (node (ref "U8") (pin "28") (pinfunction "DVCC_28") (pintype "passive"))
      (node (ref "U8") (pin "40") (pinfunction "DVCC_40") (pintype "passive"))
      (node (ref "U8") (pin "41") (pinfunction "RB_41") (pintype "passive"))
    )
    (net (code "41") (name "A3.3V") (class "Default")
      (node (ref "C21") (pin "1") (pinfunction "1_1") (pintype "passive"))
      (node (ref "C24") (pin "2") (pinfunction "2_2") (pintype "passive"))
      (node (ref "L3") (pin "1") (pinfunction "1_1") (pintype "passive"))
      (node (ref "U8") (pin "9") (pinfunction "AVCC_9") (pintype "passive"))
    )
    (net (code "42") (name "GND") (class "Default")
      (node (ref "BT1") (pin "2") (pinfunction "-_2") (pintype "passive"))
      (node (ref "C1") (pin "1") (pinfunction "1_1") (pintype "passive"))
      (node (ref "C12") (pin "2") (pinfunction "2_2") (pintype "passive"))
      (node (ref "C13") (pin "1") (pinfunction "1_1") (pintype "passive"))
      (node (ref "C15") (pin "1") (pinfunction "1_1") (pintype "passive"))
      (node (ref "C16") (pin "2") (pinfunction "2_2") (pintype "passive"))
      (node (ref "C17") (pin "2") (pinfunction "2_2") (pintype "passive"))
      (node (ref "C18") (pin "2") (pinfunction "2_2") (pintype "passive"))
      (node (ref "C19") (pin "2") (pinfunction "2_2") (pintype "passive"))
      (node (ref "C2") (pin "1") (pinfunction "1_1") (pintype "passive"))
      (node (ref "C20") (pin "1") (pinfunction "1_1") (pintype "passive"))
      (node (ref "C21") (pin "2") (pinfunction "2_2") (pintype "passive"))
      (node (ref "C22") (pin "1") (pinfunction "1_1") (pintype "passive"))
      (node (ref "C23") (pin "2") (pinfunction "2_2") (pintype "passive"))
      (node (ref "C24") (pin "1") (pinfunction "1_1") (pintype "passive"))
      (node (ref "C25") (pin "2") (pinfunction "2_2") (pintype "passive"))
      (node (ref "C26") (pin "2") (pinfunction "2_2") (pintype "passive"))
      (node (ref "C27") (pin "2") (pinfunction "2_2") (pintype "passive"))
      (node (ref "C28") (pin "2") (pinfunction "2_2") (pintype "passive"))
      (node (ref "C29") (pin "2") (pinfunction "2_2") (pintype "passive"))
      (node (ref "C3") (pin "1") (pinfunction "1_1") (pintype "passive"))
      (node (ref "C30") (pin "2") (pinfunction "2_2") (pintype "passive"))
      (node (ref "C31") (pin "2") (pinfunction "2_2") (pintype "passive"))
      (node (ref "C32") (pin "2") (pinfunction "2_2") (pintype "passive"))
      (node (ref "C33") (pin "2") (pinfunction "2_2") (pintype "passive"))
      (node (ref "C34") (pin "2") (pinfunction "2_2") (pintype "passive"))
      (node (ref "C35") (pin "2") (pinfunction "2_2") (pintype "passive"))
      (node (ref "C36") (pin "2") (pinfunction "2_2") (pintype "passive"))
      (node (ref "C37") (pin "2") (pinfunction "2_2") (pintype "passive"))
      (node (ref "C4") (pin "2") (pinfunction "2_2") (pintype "passive"))
      (node (ref "C5") (pin "2") (pinfunction "2_2") (pintype "passive"))
      (node (ref "C6") (pin "1") (pinfunction "1_1") (pintype "passive"))
      (node (ref "C7") (pin "1") (pinfunction "1_1") (pintype "passive"))
      (node (ref "C8") (pin "2") (pinfunction "2_2") (pintype "passive"))
      (node (ref "C9") (pin "2") (pinfunction "2_2") (pintype "passive"))
      (node (ref "D1") (pin "2") (pinfunction "K_2") (pintype "passive"))
      (node (ref "D10") (pin "1") (pinfunction "A_1") (pintype "passive"))
      (node (ref "D11") (pin "2") (pinfunction "K_2") (pintype "passive"))
      (node (ref "D12") (pin "1") (pinfunction "A_1") (pintype "passive"))
      (node (ref "D2") (pin "1") (pinfunction "A_1") (pintype "passive"))
      (node (ref "D3") (pin "1") (pinfunction "A_1") (pintype "passive"))
      (node (ref "D4") (pin "1") (pinfunction "A_1") (pintype "passive"))
      (node (ref "D5") (pin "1") (pinfunction "A_1") (pintype "passive"))
      (node (ref "D6") (pin "1") (pinfunction "A_1") (pintype "passive"))
      (node (ref "D7") (pin "2") (pinfunction "K_2") (pintype "passive"))
      (node (ref "D8") (pin "1") (pinfunction "A_1") (pintype "passive"))
      (node (ref "D9") (pin "2") (pinfunction "K_2") (pintype "passive"))
      (node (ref "J1") (pin "3") (pinfunction "3_3") (pintype "passive"))
      (node (ref "J10") (pin "10") (pinfunction "10_10") (pintype "passive"))
      (node (ref "J10") (pin "4") (pinfunction "4_4") (pintype "passive"))
      (node (ref "J10") (pin "6") (pinfunction "6_6") (pintype "passive"))
      (node (ref "J10") (pin "8") (pinfunction "8_8") (pintype "passive"))
      (node (ref "J2") (pin "12") (pinfunction "12_12") (pintype "passive"))
      (node (ref "J5") (pin "4") (pinfunction "4_4") (pintype "passive"))
      (node (ref "J6") (pin "3") (pinfunction "3_3") (pintype "passive"))
      (node (ref "J6") (pin "6") (pinfunction "6_6") (pintype "passive"))
      (node (ref "J7") (pin "2") (pinfunction "2_2") (pintype "power_in"))
      (node (ref "J8") (pin "10") (pinfunction "GND_10") (pintype "passive"))
      (node (ref "J8") (pin "7") (pinfunction "NC_7") (pintype "passive"))
      (node (ref "J8") (pin "8") (pinfunction "NC_8") (pintype "passive"))
      (node (ref "J8") (pin "9") (pinfunction "GND_9") (pintype "passive"))
      (node (ref "J9") (pin "10") (pinfunction "GND_10") (pintype "passive"))
      (node (ref "J9") (pin "7") (pinfunction "NC_7") (pintype "passive"))
      (node (ref "J9") (pin "8") (pinfunction "NC_8") (pintype "passive"))
      (node (ref "J9") (pin "9") (pinfunction "GND_9") (pintype "passive"))
      (node (ref "K1") (pin "2") (pinfunction "2_2") (pintype "passive"))
      (node (ref "K2") (pin "2") (pinfunction "2_2") (pintype "passive"))
      (node (ref "K3") (pin "2") (pinfunction "2_2") (pintype "passive"))
      (node (ref "K4") (pin "2") (pinfunction "2_2") (pintype "passive"))
      (node (ref "K5") (pin "2") (pinfunction "2_2") (pintype "passive"))
      (node (ref "R12") (pin "2") (pinfunction "2_2") (pintype "passive"))
      (node (ref "R14") (pin "2") (pinfunction "2_2") (pintype "passive"))
      (node (ref "U1") (pin "22") (pinfunction "GND_22") (pintype "power_in"))
      (node (ref "U1") (pin "53") (pinfunction "GND_53") (pintype "power_in"))
      (node (ref "U1") (pin "63") (pinfunction "GND_63") (pintype "power_in"))
      (node (ref "U10") (pin "1") (pinfunction "GND_1") (pintype "power_in"))
      (node (ref "U2") (pin "4") (pinfunction "GND_4") (pintype "power_in"))
      (node (ref "U3") (pin "2") (pinfunction "GND_2") (pintype "passive"))
      (node (ref "U5") (pin "5") (pinfunction "GND_5") (pintype "passive"))
      (node (ref "U6") (pin "5") (pinfunction "GND_5") (pintype "passive"))
      (node (ref "U7") (pin "4") (pinfunction "GND_4") (pintype "passive"))
      (node (ref "U8") (pin "20") (pinfunction "RA_20") (pintype "passive"))
      (node (ref "U8") (pin "29") (pinfunction "DGND_29") (pintype "passive"))
      (node (ref "U8") (pin "39") (pinfunction "DGND_39") (pintype "passive"))
      (node (ref "U8") (pin "42") (pinfunction "PM_42") (pintype "passive"))
      (node (ref "U8") (pin "43") (pinfunction "RC_43") (pintype "passive"))
      (node (ref "U8") (pin "6") (pinfunction "AGND_6") (pintype "passive"))
      (node (ref "U9") (pin "5") (pinfunction "GND_5") (pintype "power_in"))
    )
    (net (code "43") (name "Net-(BT1-+)") (class "Default")
      (node (ref "BT1") (pin "1") (pinfunction "+_1") (pintype "passive"))
      (node (ref "U2") (pin "8") (pinfunction "VCC1_8") (pintype "power_in"))
    )
    (net (code "44") (name "Net-(D1-A)") (class "Default")
      (node (ref "D1") (pin "1") (pinfunction "A_1") (pintype "passive"))
      (node (ref "R8") (pin "1") (pinfunction "1_1") (pintype "passive"))
    )
    (net (code "45") (name "Net-(D2-K)") (class "Default")
      (node (ref "D2") (pin "2") (pinfunction "K_2") (pintype "passive"))
      (node (ref "K1") (pin "4") (pinfunction "4_4") (pintype "passive"))
      (node (ref "Q1") (pin "3") (pinfunction "C_3") (pintype "passive"))
    )
    (net (code "46") (name "Net-(D3-K)") (class "Default")
      (node (ref "D3") (pin "2") (pinfunction "K_2") (pintype "passive"))
      (node (ref "K2") (pin "4") (pinfunction "4_4") (pintype "passive"))
      (node (ref "Q2") (pin "3") (pinfunction "C_3") (pintype "passive"))
    )
    (net (code "47") (name "Net-(D4-K)") (class "Default")
      (node (ref "D4") (pin "2") (pinfunction "K_2") (pintype "passive"))
      (node (ref "K3") (pin "4") (pinfunction "4_4") (pintype "passive"))
      (node (ref "Q3") (pin "3") (pinfunction "C_3") (pintype "passive"))
    )
    (net (code "48") (name "Net-(D5-K)") (class "Default")
      (node (ref "D5") (pin "2") (pinfunction "K_2") (pintype "passive"))
      (node (ref "K4") (pin "4") (pinfunction "4_4") (pintype "passive"))
      (node (ref "Q4") (pin "3") (pinfunction "C_3") (pintype "passive"))
    )
    (net (code "49") (name "Net-(D6-K)") (class "Default")
      (node (ref "D6") (pin "2") (pinfunction "K_2") (pintype "passive"))
      (node (ref "K5") (pin "4") (pinfunction "4_4") (pintype "passive"))
      (node (ref "Q5") (pin "3") (pinfunction "C_3") (pintype "passive"))
    )
    (net (code "50") (name "Net-(D7-A)") (class "Default")
      (node (ref "D7") (pin "1") (pinfunction "A_1") (pintype "passive"))
      (node (ref "J5") (pin "3") (pinfunction "3_3") (pintype "passive"))
      (node (ref "R10") (pin "2") (pinfunction "2_2") (pintype "passive"))
      (node (ref "R12") (pin "1") (pinfunction "1_1") (pintype "passive"))
      (node (ref "U5") (pin "7") (pinfunction "B_7") (pintype "passive"))
    )
    (net (code "51") (name "Net-(D8-K)") (class "Default")
      (node (ref "D8") (pin "2") (pinfunction "K_2") (pintype "passive"))
      (node (ref "J5") (pin "5") (pinfunction "5_5") (pintype "passive"))
      (node (ref "R10") (pin "1") (pinfunction "1_1") (pintype "passive"))
      (node (ref "R13") (pin "2") (pinfunction "2_2") (pintype "passive"))
      (node (ref "U5") (pin "6") (pinfunction "A_6") (pintype "passive"))
    )
    (net (code "52") (name "Net-(D9-A)") (class "Default")
      (node (ref "D9") (pin "1") (pinfunction "A_1") (pintype "passive"))
      (node (ref "J6") (pin "5") (pinfunction "5_5") (pintype "passive"))
      (node (ref "R11") (pin "2") (pinfunction "2_2") (pintype "passive"))
      (node (ref "R14") (pin "1") (pinfunction "1_1") (pintype "passive"))
      (node (ref "U6") (pin "7") (pinfunction "B_7") (pintype "passive"))
    )
    (net (code "53") (name "Net-(D10-K)") (class "Default")
      (node (ref "D10") (pin "2") (pinfunction "K_2") (pintype "passive"))
      (node (ref "J6") (pin "7") (pinfunction "7_7") (pintype "passive"))
      (node (ref "R11") (pin "1") (pinfunction "1_1") (pintype "passive"))
      (node (ref "R15") (pin "2") (pinfunction "2_2") (pintype "passive"))
      (node (ref "U6") (pin "6") (pinfunction "A_6") (pintype "passive"))
    )
    (net (code "54") (name "Net-(J3-Pad1)") (class "Default")
      (node (ref "J3") (pin "1") (pinfunction "1_1") (pintype "passive"))
      (node (ref "K2") (pin "5") (pinfunction "5_5") (pintype "passive"))
    )
    (net (code "55") (name "Net-(J3-Pad2)") (class "Default")
      (node (ref "J3") (pin "2") (pinfunction "2_2") (pintype "passive"))
      (node (ref "K2") (pin "1") (pinfunction "1_1") (pintype "passive"))
    )
    (net (code "56") (name "Net-(J3-Pad4)") (class "Default")
      (node (ref "J3") (pin "4") (pinfunction "4_4") (pintype "passive"))
      (node (ref "K3") (pin "5") (pinfunction "5_5") (pintype "passive"))
    )
    (net (code "57") (name "Net-(J3-Pad6)") (class "Default")
      (node (ref "J3") (pin "6") (pinfunction "6_6") (pintype "passive"))
      (node (ref "K4") (pin "5") (pinfunction "5_5") (pintype "passive"))
    )
    (net (code "58") (name "Net-(J5-Pad1)") (class "Default")
      (node (ref "J5") (pin "1") (pinfunction "1_1") (pintype "passive"))
      (node (ref "K5") (pin "3") (pinfunction "3_3") (pintype "passive"))
    )
    (net (code "59") (name "Net-(J5-Pad2)") (class "Default")
      (node (ref "J5") (pin "2") (pinfunction "2_2") (pintype "passive"))
      (node (ref "K5") (pin "5") (pinfunction "5_5") (pintype "passive"))
    )
    (net (code "60") (name "Net-(J8-NC-Pad4)") (class "Default")
      (node (ref "J8") (pin "4") (pinfunction "NC_4") (pintype "passive"))
      (node (ref "R20") (pin "2") (pinfunction "2_2") (pintype "passive"))
    )
    (net (code "61") (name "Net-(J8-NC-Pad5)") (class "Default")
      (node (ref "J8") (pin "5") (pinfunction "NC_5") (pintype "passive"))
      (node (ref "R21") (pin "2") (pinfunction "2_2") (pintype "passive"))
    )
    (net (code "62") (name "Net-(J8-RX+)") (class "Default")
      (node (ref "J8") (pin "3") (pinfunction "RX+_3") (pintype "passive"))
      (node (ref "R19") (pin "2") (pinfunction "2_2") (pintype "passive"))
    )
    (net (code "63") (name "Net-(J8-RX-)") (class "Default")
      (node (ref "J8") (pin "6") (pinfunction "RX-_6") (pintype "passive"))
      (node (ref "R22") (pin "2") (pinfunction "2_2") (pintype "passive"))
    )
    (net (code "64") (name "Net-(J8-TX+)") (class "Default")
      (node (ref "J8") (pin "1") (pinfunction "TX+_1") (pintype "passive"))
      (node (ref "R17") (pin "2") (pinfunction "2_2") (pintype "passive"))
    )
    (net (code "65") (name "Net-(J8-TX-)") (class "Default")
      (node (ref "J8") (pin "2") (pinfunction "TX-_2") (pintype "passive"))
      (node (ref "R18") (pin "2") (pinfunction "2_2") (pintype "passive"))
    )
    (net (code "66") (name "Net-(J9-NC-Pad4)") (class "Default")
      (node (ref "J9") (pin "4") (pinfunction "NC_4") (pintype "passive"))
      (node (ref "R26") (pin "2") (pinfunction "2_2") (pintype "passive"))
    )
    (net (code "67") (name "Net-(J9-NC-Pad5)") (class "Default")
      (node (ref "J9") (pin "5") (pinfunction "NC_5") (pintype "passive"))
      (node (ref "R27") (pin "2") (pinfunction "2_2") (pintype "passive"))
    )
    (net (code "68") (name "Net-(J9-RX+)") (class "Default")
      (node (ref "J9") (pin "3") (pinfunction "RX+_3") (pintype "passive"))
      (node (ref "R25") (pin "2") (pinfunction "2_2") (pintype "passive"))
    )
    (net (code "69") (name "Net-(J9-RX-)") (class "Default")
      (node (ref "J9") (pin "6") (pinfunction "RX-_6") (pintype "passive"))
      (node (ref "R28") (pin "2") (pinfunction "2_2") (pintype "passive"))
    )
    (net (code "70") (name "Net-(J9-TX+)") (class "Default")
      (node (ref "J9") (pin "1") (pinfunction "TX+_1") (pintype "passive"))
      (node (ref "R23") (pin "2") (pinfunction "2_2") (pintype "passive"))
    )
    (net (code "71") (name "Net-(J9-TX-)") (class "Default")
      (node (ref "J9") (pin "2") (pinfunction "TX-_2") (pintype "passive"))
      (node (ref "R24") (pin "2") (pinfunction "2_2") (pintype "passive"))
    )
    (net (code "72") (name "Net-(K1-Pad5)") (class "Default")
      (node (ref "K1") (pin "5") (pinfunction "5_5") (pintype "passive"))
      (node (ref "K2") (pin "3") (pinfunction "3_3") (pintype "passive"))
    )
    (net (code "73") (name "Net-(Q1-B)") (class "Default")
      (node (ref "Q1") (pin "1") (pinfunction "B_1") (pintype "passive"))
      (node (ref "R4") (pin "2") (pinfunction "2_2") (pintype "passive"))
    )
    (net (code "74") (name "Net-(Q1-E)") (class "Default")
      (node (ref "C8") (pin "1") (pinfunction "1_1") (pintype "passive"))
      (node (ref "L2") (pin "1") (pinfunction "1_1") (pintype "passive"))
      (node (ref "Q1") (pin "2") (pinfunction "E_2") (pintype "passive"))
      (node (ref "Q2") (pin "2") (pinfunction "E_2") (pintype "passive"))
      (node (ref "Q3") (pin "2") (pinfunction "E_2") (pintype "passive"))
      (node (ref "Q4") (pin "2") (pinfunction "E_2") (pintype "passive"))
      (node (ref "Q5") (pin "2") (pinfunction "E_2") (pintype "passive"))
      (node (ref "R31") (pin "1") (pinfunction "1_1") (pintype "passive"))
      (node (ref "R32") (pin "1") (pinfunction "1_1") (pintype "passive"))
      (node (ref "R33") (pin "1") (pinfunction "1_1") (pintype "passive"))
      (node (ref "R34") (pin "1") (pinfunction "1_1") (pintype "passive"))
      (node (ref "R35") (pin "2") (pinfunction "2_2") (pintype "passive"))
    )
    (net (code "75") (name "Net-(Q2-B)") (class "Default")
      (node (ref "Q2") (pin "1") (pinfunction "B_1") (pintype "passive"))
      (node (ref "R5") (pin "2") (pinfunction "2_2") (pintype "passive"))
    )
    (net (code "76") (name "Net-(Q3-B)") (class "Default")
      (node (ref "Q3") (pin "1") (pinfunction "B_1") (pintype "passive"))
      (node (ref "R6") (pin "2") (pinfunction "2_2") (pintype "passive"))
    )
    (net (code "77") (name "Net-(Q4-B)") (class "Default")
      (node (ref "Q4") (pin "1") (pinfunction "B_1") (pintype "passive"))
      (node (ref "R7") (pin "2") (pinfunction "2_2") (pintype "passive"))
    )
    (net (code "78") (name "Net-(Q5-B)") (class "Default")
      (node (ref "Q5") (pin "1") (pinfunction "B_1") (pintype "passive"))
      (node (ref "R9") (pin "1") (pinfunction "1_1") (pintype "passive"))
    )
    (net (code "79") (name "Net-(U1-AVCC)") (class "Default")
      (node (ref "C6") (pin "2") (pinfunction "2_2") (pintype "passive"))
      (node (ref "L1") (pin "2") (pinfunction "2_2") (pintype "passive"))
      (node (ref "U1") (pin "64") (pinfunction "AVCC_64") (pintype "power_in"))
    )
    (net (code "80") (name "Net-(U1-XTAL1)") (class "Default")
      (node (ref "C2") (pin "2") (pinfunction "2_2") (pintype "passive"))
      (node (ref "U1") (pin "24") (pinfunction "XTAL1_24") (pintype "passive"))
      (node (ref "Y1") (pin "1") (pinfunction "OSC1_1") (pintype "passive"))
    )
    (net (code "81") (name "Net-(U1-XTAL2)") (class "Default")
      (node (ref "C1") (pin "2") (pinfunction "2_2") (pintype "passive"))
      (node (ref "U1") (pin "23") (pinfunction "XTAL2_23") (pintype "passive"))
      (node (ref "Y1") (pin "2") (pinfunction "OSC2_2") (pintype "passive"))
    )
    (net (code "82") (name "Net-(U2-X1)") (class "Default")
      (node (ref "U2") (pin "2") (pinfunction "X1_2") (pintype "input"))
      (node (ref "Y2") (pin "1") (pinfunction "OSC1_1") (pintype "passive"))
    )
    (net (code "83") (name "Net-(U2-X2)") (class "Default")
      (node (ref "U2") (pin "3") (pinfunction "X2_3") (pintype "input"))
      (node (ref "Y2") (pin "2") (pinfunction "OSC2_2") (pintype "passive"))
    )
    (net (code "84") (name "Net-(U4-GND)") (class "Default")
      (node (ref "C10") (pin "2") (pinfunction "2_2") (pintype "passive"))
      (node (ref "C11") (pin "2") (pinfunction "2_2") (pintype "passive"))
      (node (ref "J7") (pin "3") (pinfunction "3_3") (pintype "power_in"))
      (node (ref "U4") (pin "4") (pinfunction "GND_4") (pintype "passive"))
    )
    (net (code "85") (name "Net-(U4-L)") (class "Default")
      (node (ref "J4") (pin "1") (pinfunction "1_1") (pintype "passive"))
      (node (ref "K1") (pin "3") (pinfunction "3_3") (pintype "passive"))
      (node (ref "K3") (pin "3") (pinfunction "3_3") (pintype "passive"))
      (node (ref "K4") (pin "3") (pinfunction "3_3") (pintype "passive"))
      (node (ref "U4") (pin "1") (pinfunction "L_1") (pintype "passive"))
    )
    (net (code "86") (name "Net-(U4-N)") (class "Default")
      (node (ref "J3") (pin "3") (pinfunction "3_3") (pintype "passive"))
      (node (ref "J3") (pin "5") (pinfunction "5_5") (pintype "passive"))
      (node (ref "J3") (pin "7") (pinfunction "7_7") (pintype "passive"))
      (node (ref "J4") (pin "2") (pinfunction "2_2") (pintype "passive"))
      (node (ref "U4") (pin "2") (pinfunction "N_2") (pintype "passive"))
    )
    (net (code "87") (name "Net-(U4-VO+)") (class "Default")
      (node (ref "C10") (pin "1") (pinfunction "1_1") (pintype "passive"))
      (node (ref "C11") (pin "1") (pinfunction "1_1") (pintype "passive"))
      (node (ref "F1") (pin "1") (pinfunction "1_1") (pintype "passive"))
      (node (ref "J7") (pin "1") (pinfunction "1_1") (pintype "power_in"))
      (node (ref "U4") (pin "3") (pinfunction "VO+_3") (pintype "passive"))
    )
    (net (code "88") (name "Net-(U8-IBN)") (class "Default")
      (node (ref "C36") (pin "1") (pinfunction "1_1") (pintype "passive"))
      (node (ref "R28") (pin "1") (pinfunction "1_1") (pintype "passive"))
      (node (ref "U8") (pin "8") (pinfunction "IBN_8") (pintype "passive"))
    )
    (net (code "89") (name "Net-(U8-IBP)") (class "Default")
      (node (ref "C33") (pin "1") (pinfunction "1_1") (pintype "passive"))
      (node (ref "R25") (pin "1") (pinfunction "1_1") (pintype "passive"))
      (node (ref "U8") (pin "7") (pinfunction "IBP_7") (pintype "passive"))
    )
    (net (code "90") (name "Net-(U8-ICN)") (class "Default")
      (node (ref "C34") (pin "1") (pinfunction "1_1") (pintype "passive"))
      (node (ref "R26") (pin "1") (pinfunction "1_1") (pintype "passive"))
      (node (ref "U8") (pin "11") (pinfunction "ICN_11") (pintype "passive"))
    )
    (net (code "91") (name "Net-(U8-ICP)") (class "Default")
      (node (ref "C35") (pin "1") (pinfunction "1_1") (pintype "passive"))
      (node (ref "R27") (pin "1") (pinfunction "1_1") (pintype "passive"))
      (node (ref "U8") (pin "10") (pinfunction "ICP_10") (pintype "passive"))
    )
    (net (code "92") (name "Net-(U8-LAN)") (class "Default")
      (node (ref "C32") (pin "1") (pinfunction "1_1") (pintype "passive"))
      (node (ref "R24") (pin "1") (pinfunction "1_1") (pintype "passive"))
      (node (ref "U8") (pin "5") (pinfunction "LAN_5") (pintype "passive"))
    )
    (net (code "93") (name "Net-(U8-LAP)") (class "Default")
      (node (ref "C31") (pin "1") (pinfunction "1_1") (pintype "passive"))
      (node (ref "R23") (pin "1") (pinfunction "1_1") (pintype "passive"))
      (node (ref "U8") (pin "4") (pinfunction "LAP_4") (pintype "passive"))
    )
    (net (code "94") (name "Net-(U8-REFV)") (class "Default")
      (node (ref "C18") (pin "1") (pinfunction "1_1") (pintype "passive"))
      (node (ref "C20") (pin "2") (pinfunction "2_2") (pintype "passive"))
      (node (ref "U8") (pin "3") (pinfunction "REFV_3") (pintype "passive"))
    )
    (net (code "95") (name "Net-(U8-VAN)") (class "Default")
      (node (ref "C29") (pin "1") (pinfunction "1_1") (pintype "passive"))
      (node (ref "R18") (pin "1") (pinfunction "1_1") (pintype "passive"))
      (node (ref "U8") (pin "13") (pinfunction "VAN_13") (pintype "passive"))
    )
    (net (code "96") (name "Net-(U8-VAP)") (class "Default")
      (node (ref "C30") (pin "1") (pinfunction "1_1") (pintype "passive"))
      (node (ref "R17") (pin "1") (pinfunction "1_1") (pintype "passive"))
      (node (ref "U8") (pin "12") (pinfunction "VAP_12") (pintype "passive"))
    )
    (net (code "97") (name "Net-(U8-VBN)") (class "Default")
      (node (ref "C27") (pin "1") (pinfunction "1_1") (pintype "passive"))
      (node (ref "R22") (pin "1") (pinfunction "1_1") (pintype "passive"))
      (node (ref "U8") (pin "15") (pinfunction "VBN_15") (pintype "passive"))
    )
    (net (code "98") (name "Net-(U8-VBP)") (class "Default")
      (node (ref "C28") (pin "1") (pinfunction "1_1") (pintype "passive"))
      (node (ref "R19") (pin "1") (pinfunction "1_1") (pintype "passive"))
      (node (ref "U8") (pin "14") (pinfunction "VBP_14") (pintype "passive"))
    )
    (net (code "99") (name "Net-(U8-VCN)") (class "Default")
      (node (ref "C25") (pin "1") (pinfunction "1_1") (pintype "passive"))
      (node (ref "R20") (pin "1") (pinfunction "1_1") (pintype "passive"))
      (node (ref "U8") (pin "17") (pinfunction "VCN_17") (pintype "passive"))
    )
    (net (code "100") (name "Net-(U8-VCP)") (class "Default")
      (node (ref "C26") (pin "1") (pinfunction "1_1") (pintype "passive"))
      (node (ref "R21") (pin "1") (pinfunction "1_1") (pintype "passive"))
      (node (ref "U8") (pin "16") (pinfunction "VCP_16") (pintype "passive"))
    )
    (net (code "101") (name "Net-(U8-VO)") (class "Default")
      (node (ref "C17") (pin "1") (pinfunction "1_1") (pintype "passive"))
      (node (ref "C19") (pin "1") (pinfunction "1_1") (pintype "passive"))
      (node (ref "U8") (pin "38") (pinfunction "VO_38") (pintype "passive"))
    )
    (net (code "102") (name "Net-(U8-XI)") (class "Default")
      (node (ref "C15") (pin "2") (pinfunction "2_2") (pintype "passive"))
      (node (ref "R16") (pin "1") (pinfunction "1_1") (pintype "passive"))
      (node (ref "U8") (pin "37") (pinfunction "XI_37") (pintype "passive"))
      (node (ref "Y3") (pin "1") (pinfunction "OSC1_1") (pintype "passive"))
    )
    (net (code "103") (name "Net-(U8-XO)") (class "Default")
      (node (ref "C16") (pin "1") (pinfunction "1_1") (pintype "passive"))
      (node (ref "R16") (pin "2") (pinfunction "2_2") (pintype "passive"))
      (node (ref "U8") (pin "36") (pinfunction "XO_36") (pintype "passive"))
      (node (ref "Y3") (pin "2") (pinfunction "OSC2_2") (pintype "passive"))
    )
    (net (code "104") (name "VCC") (class "Default")
      (node (ref "C12") (pin "1") (pinfunction "1_1") (pintype "passive"))
      (node (ref "C13") (pin "2") (pinfunction "2_2") (pintype "passive"))
      (node (ref "C37") (pin "1") (pinfunction "1_1") (pintype "passive"))
      (node (ref "C4") (pin "1") (pinfunction "1_1") (pintype "passive"))
      (node (ref "C5") (pin "1") (pinfunction "1_1") (pintype "passive"))
      (node (ref "C7") (pin "2") (pinfunction "2_2") (pintype "passive"))
      (node (ref "C9") (pin "1") (pinfunction "1_1") (pintype "passive"))
      (node (ref "F1") (pin "2") (pinfunction "2_2") (pintype "passive"))
      (node (ref "J1") (pin "2") (pinfunction "2_2") (pintype "passive"))
      (node (ref "J10") (pin "2") (pinfunction "2_2") (pintype "passive"))
      (node (ref "J2") (pin "11") (pinfunction "11_11") (pintype "passive"))
      (node (ref "J6") (pin "1") (pinfunction "1_1") (pintype "passive"))
      (node (ref "L1") (pin "1") (pinfunction "1_1") (pintype "passive"))
      (node (ref "L2") (pin "2") (pinfunction "2_2") (pintype "passive"))
      (node (ref "R1") (pin "1") (pinfunction "1_1") (pintype "passive"))
      (node (ref "R13") (pin "1") (pinfunction "1_1") (pintype "passive"))
      (node (ref "R15") (pin "1") (pinfunction "1_1") (pintype "passive"))
      (node (ref "R2") (pin "1") (pinfunction "1_1") (pintype "passive"))
      (node (ref "R29") (pin "1") (pinfunction "1_1") (pintype "passive"))
      (node (ref "R3") (pin "1") (pinfunction "1_1") (pintype "passive"))
      (node (ref "R30") (pin "2") (pinfunction "2_2") (pintype "passive"))
      (node (ref "R8") (pin "2") (pinfunction "2_2") (pintype "passive"))
      (node (ref "U1") (pin "21") (pinfunction "VCC_21") (pintype "power_in"))
      (node (ref "U1") (pin "52") (pinfunction "VCC_52") (pintype "power_in"))
      (node (ref "U10") (pin "3") (pinfunction "IN_3") (pintype "power_in"))
      (node (ref "U2") (pin "1") (pinfunction "VCC2_1") (pintype "power_in"))
      (node (ref "U3") (pin "1") (pinfunction "VIN_1") (pintype "passive"))
      (node (ref "U3") (pin "5") (pinfunction "AD_5") (pintype "passive"))
      (node (ref "U5") (pin "2") (pinfunction "~{RE}_2") (pintype "passive"))
      (node (ref "U5") (pin "3") (pinfunction "~{SHDN}_3") (pintype "passive"))
      (node (ref "U5") (pin "8") (pinfunction "VCC_8") (pintype "passive"))
      (node (ref "U6") (pin "2") (pinfunction "~{RE}_2") (pintype "passive"))
      (node (ref "U6") (pin "3") (pinfunction "~{SHDN}_3") (pintype "passive"))
      (node (ref "U6") (pin "8") (pinfunction "VCC_8") (pintype "passive"))
      (node (ref "U7") (pin "8") (pinfunction "VCC_8") (pintype "passive"))
      (node (ref "U9") (pin "8") (pinfunction "VCC_8") (pintype "power_in"))
    )
    (net (code "105") (name "unconnected-(J1-Pad1)") (class "Default")
      (node (ref "J1") (pin "1") (pinfunction "1_1") (pintype "passive"))
    )
    (net (code "106") (name "unconnected-(J10-Pad3)") (class "Default")
      (node (ref "J10") (pin "3") (pinfunction "3_3") (pintype "passive"))
    )
    (net (code "107") (name "unconnected-(K1-Pad1)") (class "Default")
      (node (ref "K1") (pin "1") (pinfunction "1_1") (pintype "passive"))
    )
    (net (code "108") (name "unconnected-(K3-Pad1)") (class "Default")
      (node (ref "K3") (pin "1") (pinfunction "1_1") (pintype "passive"))
    )
    (net (code "109") (name "unconnected-(K4-Pad1)") (class "Default")
      (node (ref "K4") (pin "1") (pinfunction "1_1") (pintype "passive"))
    )
    (net (code "110") (name "unconnected-(K5-Pad1)") (class "Default")
      (node (ref "K5") (pin "1") (pinfunction "1_1") (pintype "passive"))
    )
    (net (code "111") (name "unconnected-(U1-AREF-Pad62)") (class "Default")
      (node (ref "U1") (pin "62") (pinfunction "AREF_62") (pintype "passive"))
    )
    (net (code "112") (name "unconnected-(U1-PA0_(AD0)-Pad51)") (class "Default")
      (node (ref "U1") (pin "51") (pinfunction "PA0_(AD0)_51") (pintype "bidirectional"))
    )
    (net (code "113") (name "unconnected-(U1-PA1_(AD1)-Pad50)") (class "Default")
      (node (ref "U1") (pin "50") (pinfunction "PA1_(AD1)_50") (pintype "bidirectional"))
    )
    (net (code "114") (name "unconnected-(U1-PA2_(AD2)-Pad49)") (class "Default")
      (node (ref "U1") (pin "49") (pinfunction "PA2_(AD2)_49") (pintype "bidirectional"))
    )
    (net (code "115") (name "unconnected-(U1-PA3_(AD3)-Pad48)") (class "Default")
      (node (ref "U1") (pin "48") (pinfunction "PA3_(AD3)_48") (pintype "bidirectional"))
    )
    (net (code "116") (name "unconnected-(U1-PA4_(AD4)-Pad47)") (class "Default")
      (node (ref "U1") (pin "47") (pinfunction "PA4_(AD4)_47") (pintype "bidirectional"))
    )
    (net (code "117") (name "unconnected-(U1-PA5_(AD5)-Pad46)") (class "Default")
      (node (ref "U1") (pin "46") (pinfunction "PA5_(AD5)_46") (pintype "bidirectional"))
    )
    (net (code "118") (name "unconnected-(U1-PA6_(AD6)-Pad45)") (class "Default")
      (node (ref "U1") (pin "45") (pinfunction "PA6_(AD6)_45") (pintype "bidirectional"))
    )
    (net (code "119") (name "unconnected-(U1-PA7_(AD7)-Pad44)") (class "Default")
      (node (ref "U1") (pin "44") (pinfunction "PA7_(AD7)_44") (pintype "bidirectional"))
    )
    (net (code "120") (name "unconnected-(U1-PB7_(OC2{slash}OC1C)-Pad17)") (class "Default")
      (node (ref "U1") (pin "17") (pinfunction "PB7_(OC2/OC1C)_17") (pintype "bidirectional"))
    )
    (net (code "121") (name "unconnected-(U1-PC3_(A11)-Pad38)") (class "Default")
      (node (ref "U1") (pin "38") (pinfunction "PC3_(A11)_38") (pintype "bidirectional"))
    )
    (net (code "122") (name "unconnected-(U1-PC4_(A12)-Pad39)") (class "Default")
      (node (ref "U1") (pin "39") (pinfunction "PC4_(A12)_39") (pintype "bidirectional"))
    )
    (net (code "123") (name "unconnected-(U1-PC5_(A13)-Pad40)") (class "Default")
      (node (ref "U1") (pin "40") (pinfunction "PC5_(A13)_40") (pintype "bidirectional"))
    )
    (net (code "124") (name "unconnected-(U1-PC6_(A14)-Pad41)") (class "Default")
      (node (ref "U1") (pin "41") (pinfunction "PC6_(A14)_41") (pintype "bidirectional"))
    )
    (net (code "125") (name "unconnected-(U1-PC7_(A15)-Pad42)") (class "Default")
      (node (ref "U1") (pin "42") (pinfunction "PC7_(A15)_42") (pintype "bidirectional"))
    )
    (net (code "126") (name "unconnected-(U1-PG2_(ALE)-Pad43)") (class "Default")
      (node (ref "U1") (pin "43") (pinfunction "PG2_(ALE)_43") (pintype "bidirectional"))
    )
    (net (code "127") (name "unconnected-(U1-TOSC1{slash}1PG4-Pad19)") (class "Default")
      (node (ref "U1") (pin "19") (pinfunction "TOSC1/1PG4_19") (pintype "bidirectional"))
    )
    (net (code "128") (name "unconnected-(U1-TOSC2{slash}PG3-Pad18)") (class "Default")
      (node (ref "U1") (pin "18") (pinfunction "TOSC2/PG3_18") (pintype "bidirectional"))
    )
    (net (code "129") (name "unconnected-(U1-~{PEN}-Pad1)") (class "Default")
      (node (ref "U1") (pin "1") (pinfunction "~{PEN}_1") (pintype "input"))
    )
    (net (code "130") (name "unconnected-(U3-AL-Pad6)") (class "Default")
      (node (ref "U3") (pin "6") (pinfunction "AL_6") (pintype "passive"))
    )
    (net (code "131") (name "unconnected-(U8-CF1-Pad26)") (class "Default")
      (node (ref "U8") (pin "26") (pinfunction "CF1_26") (pintype "passive"))
    )
    (net (code "132") (name "unconnected-(U8-CF2-Pad25)") (class "Default")
      (node (ref "U8") (pin "25") (pinfunction "CF2_25") (pintype "passive"))
    )
    (net (code "133") (name "unconnected-(U8-CF3-Pad24)") (class "Default")
      (node (ref "U8") (pin "24") (pinfunction "CF3_24") (pintype "passive"))
    )
    (net (code "134") (name "unconnected-(U8-CF4-Pad23)") (class "Default")
      (node (ref "U8") (pin "23") (pinfunction "CF4_23") (pintype "passive"))
    )
    (net (code "135") (name "unconnected-(U8-CTT-Pad22)") (class "Default")
      (node (ref "U8") (pin "22") (pinfunction "CTT_22") (pintype "passive"))
    )
    (net (code "136") (name "unconnected-(U8-INN-Pad19)") (class "Default")
      (node (ref "U8") (pin "19") (pinfunction "INN_19") (pintype "passive"))
    )
    (net (code "137") (name "unconnected-(U8-INP-Pad18)") (class "Default")
      (node (ref "U8") (pin "18") (pinfunction "INP_18") (pintype "passive"))
    )
    (net (code "138") (name "unconnected-(U8-INTN-Pad31)") (class "Default")
      (node (ref "U8") (pin "31") (pinfunction "INTN_31") (pintype "passive"))
    )
    (net (code "139") (name "unconnected-(U8-NC-Pad1)") (class "Default")
      (node (ref "U8") (pin "1") (pinfunction "NC_1") (pintype "passive"))
    )
    (net (code "140") (name "unconnected-(U8-NC-Pad2)") (class "Default")
      (node (ref "U8") (pin "2") (pinfunction "NC_2") (pintype "passive"))
    )
    (net (code "141") (name "unconnected-(U8-NC-Pad21)") (class "Default")
      (node (ref "U8") (pin "21") (pinfunction "NC_21") (pintype "passive"))
    )
    (net (code "142") (name "unconnected-(U8-NC-Pad30)") (class "Default")
      (node (ref "U8") (pin "30") (pinfunction "NC_30") (pintype "passive"))
    )
    (net (code "143") (name "unconnected-(U8-NC-Pad44)") (class "Default")
      (node (ref "U8") (pin "44") (pinfunction "NC_44") (pintype "passive"))
    )
    (net (code "144") (name "unconnected-(U9-DC-Pad7)") (class "Default")
      (node (ref "U9") (pin "7") (pinfunction "DC_7") (pintype "passive"))
    )
    (net (code "145") (name "unconnected-(U9-ORG-Pad6)") (class "Default")
      (node (ref "U9") (pin "6") (pinfunction "ORG_6") (pintype "passive"))
    )
  )
)
